# power.net
KiCad netlist of a schematic drawn in Altium Designer
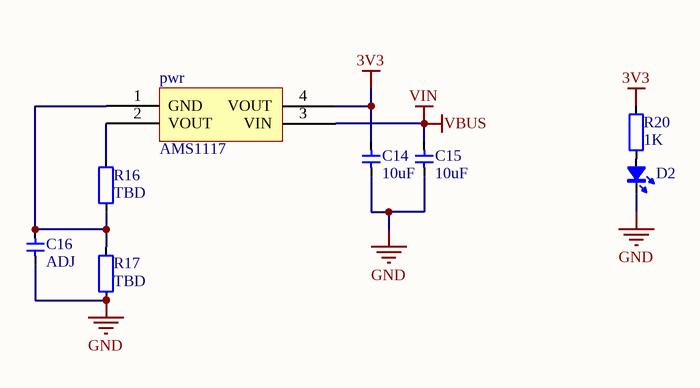
[diagram p0: power.SchDoc]

(export (version "E")
  (design (tool "Eeschema 10.0.6"))
  (components
    (comp (ref "C14")
      (value "10uF")
      (footprint "C0603")
      (description "Capacitor")
      (libsource (lib "MyPcbLib") (part "电容-0402"))
    )
    (comp (ref "C15")
      (value "10uF")
      (footprint "C0603")
      (description "Capacitor")
      (libsource (lib "MyPcbLib") (part "电容-0402"))
    )
    (comp (ref "C16")
      (value "ADJ")
      (footprint "C0603")
      (description "Capacitor")
      (libsource (lib "MyPcbLib") (part "电容-0402"))
    )
    (comp (ref "D2")
      (value "color?")
      (footprint "LED_0402_RED")
      (description "LED")
      (libsource (lib "KitSprout") (part "LED_0402"))
    )
    (comp (ref "pwr") (value "AMS1117") (footprint "SOT223_L") (libsource (lib "ESP_SCH") (part "AMS1117")))
    (comp (ref "R16")
      (value "TBD")
      (footprint "R0603")
      (description "Resistor")
      (libsource (lib "MyPcbLib") (part "电阻-0402"))
    )
    (comp (ref "R17")
      (value "TBD")
      (footprint "R0603")
      (description "Resistor")
      (libsource (lib "MyPcbLib") (part "电阻-0402"))
    )
    (comp (ref "R20")
      (value "1K")
      (footprint "RES_0402")
      (description "Resistor")
      (libsource (lib "MyPcbLib") (part "电阻-0402"))
    )
  )
  (nets
    (net (code "1") (name "3V3") (class "Default")
      (node (ref "C14") (pin "2") (pinfunction "2_2") (pintype "passive"))
      (node (ref "R20") (pin "1") (pinfunction "1_1") (pintype "passive"))
      (node (ref "pwr") (pin "4") (pinfunction "VOUT_4") (pintype "passive"))
    )
    (net (code "2") (name "GND") (class "Default")
      (node (ref "C14") (pin "1") (pinfunction "1_1") (pintype "passive"))
      (node (ref "C15") (pin "1") (pinfunction "1_1") (pintype "passive"))
      (node (ref "C16") (pin "1") (pinfunction "1_1") (pintype "passive"))
      (node (ref "D2") (pin "2") (pinfunction "K_2") (pintype "passive"))
      (node (ref "R17") (pin "2") (pinfunction "2_2") (pintype "passive"))
    )
    (net (code "3") (name "Net-(D2-A)") (class "Default")
      (node (ref "D2") (pin "1") (pinfunction "A_1") (pintype "passive"))
      (node (ref "R20") (pin "2") (pinfunction "2_2") (pintype "passive"))
    )
    (net (code "4") (name "Net-(R16-Pad1)") (class "Default")
      (node (ref "R16") (pin "1") (pinfunction "1_1") (pintype "passive"))
      (node (ref "pwr") (pin "2") (pinfunction "VOUT_2") (pintype "passive"))
    )
    (net (code "5") (name "Net-(pwr-GND)") (class "Default")
      (node (ref "C16") (pin "2") (pinfunction "2_2") (pintype "passive"))
      (node (ref "R16") (pin "2") (pinfunction "2_2") (pintype "passive"))
      (node (ref "R17") (pin "1") (pinfunction "1_1") (pintype "passive"))
      (node (ref "pwr") (pin "1") (pinfunction "GND_1") (pintype "passive"))
    )
    (net (code "6") (name "VBUS") (class "Default")
      (node (ref "C15") (pin "2") (pinfunction "2_2") (pintype "passive"))
      (node (ref "pwr") (pin "3") (pinfunction "VIN_3") (pintype "passive"))
    )
  )
)
